# amp_schematic1.net
KiCad netlist of a schematic drawn in EAGLE
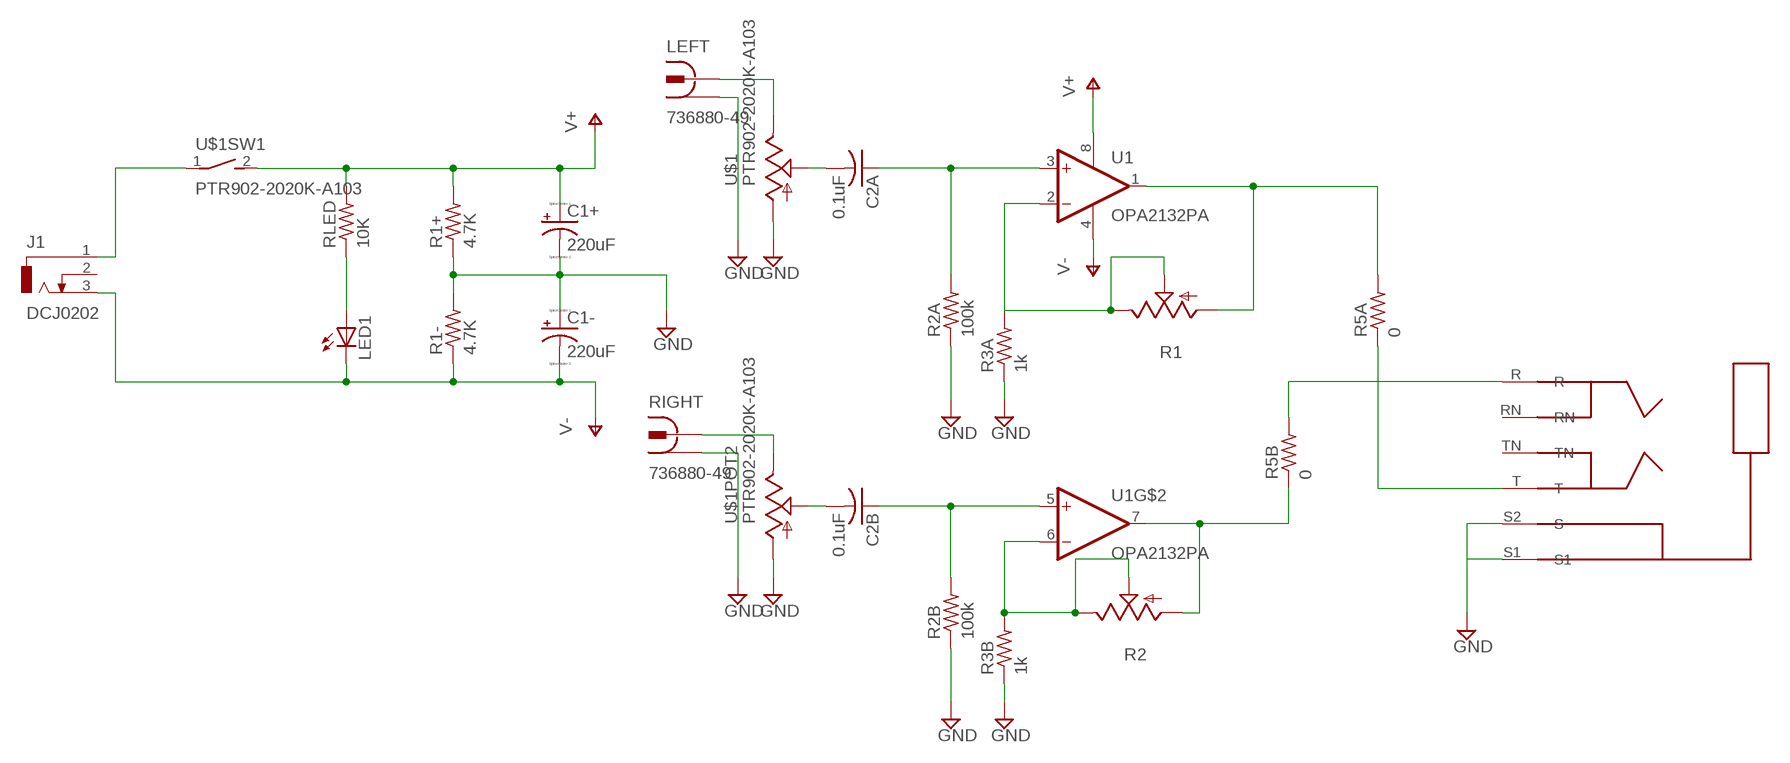
[diagram p0: schematic, sheet 1]

(export (version "E")
  (design (tool "Eeschema 10.0.6"))
  (components
    (comp (ref "C1+")
      (value "220uF")
      (footprint "eagle-import:E3,5-8")
      (libsource (lib "eagle-import") (part "CPOL-USE3.5-8"))
    )
    (comp (ref "C1-")
      (value "220uF")
      (footprint "eagle-import:E3,5-8")
      (libsource (lib "eagle-import") (part "CPOL-USE3.5-8"))
    )
    (comp (ref "C2A")
      (value "0.1uF")
      (footprint "eagle-import:C050-025X075")
      (libsource (lib "eagle-import") (part "C-US050-025X075"))
    )
    (comp (ref "C2B")
      (value "0.1uF")
      (footprint "eagle-import:C050-025X075")
      (libsource (lib "eagle-import") (part "C-US050-025X075"))
    )
    (comp (ref "J1")
      (value "DCJ0202")
      (footprint "eagle-import:DCJ0202")
      (libsource (lib "eagle-import") (part "DCJ0202"))
    )
    (comp (ref "LED1")
      (value "LED5MM")
      (footprint "eagle-import:LED5MM")
      (libsource (lib "eagle-import") (part "LED5MM"))
    )
    (comp (ref "LEFT")
      (value "736880-49")
      (footprint "eagle-import:736880-49")
      (libsource (lib "eagle-import") (part "736880-49"))
    )
    (comp (ref "R1")
      (value "TRIM_US-B25U")
      (footprint "eagle-import:B25U")
      (libsource (lib "eagle-import") (part "TRIM_US-B25U"))
    )
    (comp (ref "R1+")
      (value "4.7K")
      (footprint "eagle-import:0204V")
      (libsource (lib "eagle-import") (part "R-US_0204/2V"))
    )
    (comp (ref "R1-")
      (value "4.7K")
      (footprint "eagle-import:0204V")
      (libsource (lib "eagle-import") (part "R-US_0204/2V"))
    )
    (comp (ref "R2")
      (value "TRIM_US-B25U")
      (footprint "eagle-import:B25U")
      (libsource (lib "eagle-import") (part "TRIM_US-B25U"))
    )
    (comp (ref "R2A")
      (value "100k")
      (footprint "eagle-import:0204V")
      (libsource (lib "eagle-import") (part "R-US_0204/2V"))
    )
    (comp (ref "R2B")
      (value "100k")
      (footprint "eagle-import:0204V")
      (libsource (lib "eagle-import") (part "R-US_0204/2V"))
    )
    (comp (ref "R3A")
      (value "1k")
      (footprint "eagle-import:0204V")
      (libsource (lib "eagle-import") (part "R-US_0204/2V"))
    )
    (comp (ref "R3B")
      (value "1k")
      (footprint "eagle-import:0204V")
      (libsource (lib "eagle-import") (part "R-US_0204/2V"))
    )
    (comp (ref "R5A")
      (value "0")
      (footprint "eagle-import:0204V")
      (libsource (lib "eagle-import") (part "R-US_0204/2V"))
    )
    (comp (ref "R5B")
      (value "0")
      (footprint "eagle-import:0204V")
      (libsource (lib "eagle-import") (part "R-US_0204/2V"))
    )
    (comp (ref "RIGHT")
      (value "736880-49")
      (footprint "eagle-import:736880-49")
      (libsource (lib "eagle-import") (part "736880-49"))
    )
    (comp (ref "RLED")
      (value "10K")
      (footprint "eagle-import:0204V")
      (libsource (lib "eagle-import") (part "R-US_0204/2V"))
    )
    (comp (ref "U$1")
      (value "PTR902-2020K-A103")
      (footprint "eagle-import:PTR902")
      (libsource (lib "eagle-import") (part "PTR902-2020K-A103"))
    )
    (comp (ref "U$2")
      (value "STEROJACK")
      (footprint "eagle-import:STEREOJACK")
      (libsource (lib "eagle-import") (part "STEROJACK"))
    )
    (comp (ref "U1")
      (value "OPA2132PA")
      (footprint "eagle-import:DIP254P762X508-8")
      (fields (field (name "DIGI-KEY_PART_NUMBER") "OPA2132PA-ND") (field (name "MF") "Texas Instruments"))
      (libsource (lib "eagle-import") (part "OPA2132PA"))
    )
  )
  (nets
    (net (code "1") (name "GND") (class "Default")
      (node (ref "C1+") (pin "-") (pinfunction "-_-") (pintype "passive"))
      (node (ref "C1-") (pin "+") (pinfunction "+_+") (pintype "passive"))
      (node (ref "LEFT") (pin "1") (pinfunction "1_1") (pintype "passive"))
      (node (ref "LEFT") (pin "1@1") (pinfunction "1_1@1") (pintype "passive"))
      (node (ref "LEFT") (pin "1@2") (pinfunction "1_1@2") (pintype "passive"))
      (node (ref "R1+") (pin "1") (pinfunction "1_1") (pintype "passive"))
      (node (ref "R1-") (pin "2") (pinfunction "2_2") (pintype "passive"))
      (node (ref "R2A") (pin "1") (pinfunction "1_1") (pintype "passive"))
      (node (ref "R2B") (pin "1") (pinfunction "1_1") (pintype "passive"))
      (node (ref "R3A") (pin "1") (pinfunction "1_1") (pintype "passive"))
      (node (ref "R3B") (pin "1") (pinfunction "1_1") (pintype "passive"))
      (node (ref "RIGHT") (pin "1") (pinfunction "1_1") (pintype "passive"))
      (node (ref "RIGHT") (pin "1@1") (pinfunction "1_1@1") (pintype "passive"))
      (node (ref "RIGHT") (pin "1@2") (pinfunction "1_1@2") (pintype "passive"))
      (node (ref "U$1") (pin "1A") (pinfunction "A_1A") (pintype "passive"))
      (node (ref "U$1") (pin "1B") (pinfunction "A_1B") (pintype "passive"))
      (node (ref "U$2") (pin "S1") (pinfunction "S1_S1") (pintype "bidirectional"))
      (node (ref "U$2") (pin "S2") (pinfunction "S_S2") (pintype "bidirectional"))
    )
    (net (code "2") (name "Net-(LED1-PadA)") (class "Default")
      (node (ref "LED1") (pin "A") (pinfunction "A_A") (pintype "passive"))
      (node (ref "RLED") (pin "1") (pinfunction "1_1") (pintype "passive"))
    )
    (net (code "3") (name "Net-(R5A-Pad1)") (class "Default")
      (node (ref "R5A") (pin "1") (pinfunction "1_1") (pintype "passive"))
      (node (ref "U$2") (pin "T") (pinfunction "T_T") (pintype "bidirectional"))
    )
    (net (code "4") (name "Net-(R5B-Pad2)") (class "Default")
      (node (ref "R5B") (pin "2") (pinfunction "2_2") (pintype "passive"))
      (node (ref "U$2") (pin "R") (pinfunction "R_R") (pintype "bidirectional"))
    )
    (net (code "5") (name "Net-(U$1A-E)") (class "Default")
      (node (ref "LEFT") (pin "2") (pinfunction "2_2") (pintype "passive"))
      (node (ref "U$1") (pin "3A") (pinfunction "E_3A") (pintype "passive"))
    )
    (net (code "6") (name "Net-(U$1A-S)") (class "Default")
      (node (ref "C2A") (pin "2") (pinfunction "2_2") (pintype "passive"))
      (node (ref "U$1") (pin "2A") (pinfunction "S_2A") (pintype "passive"))
    )
    (net (code "7") (name "Net-(U$1B-E)") (class "Default")
      (node (ref "RIGHT") (pin "2") (pinfunction "2_2") (pintype "passive"))
      (node (ref "U$1") (pin "3B") (pinfunction "E_3B") (pintype "passive"))
    )
    (net (code "8") (name "Net-(U$1B-S)") (class "Default")
      (node (ref "C2B") (pin "2") (pinfunction "2_2") (pintype "passive"))
      (node (ref "U$1") (pin "2B") (pinfunction "S_2B") (pintype "passive"))
    )
    (net (code "9") (name "Net-(U$1C-P)") (class "Default")
      (node (ref "J1") (pin "1") (pinfunction "1_1") (pintype "passive"))
      (node (ref "U$1") (pin "1") (pinfunction "P_1") (pintype "passive"))
    )
    (net (code "10") (name "Net-(U1A-+INA)") (class "Default")
      (node (ref "C2A") (pin "1") (pinfunction "1_1") (pintype "passive"))
      (node (ref "R2A") (pin "2") (pinfunction "2_2") (pintype "passive"))
      (node (ref "U1") (pin "3") (pinfunction "+INA_3") (pintype "input"))
    )
    (net (code "11") (name "Net-(U1A--INA)") (class "Default")
      (node (ref "R1") (pin "E") (pinfunction "E_E") (pintype "passive"))
      (node (ref "R1") (pin "S") (pinfunction "S_S") (pintype "passive"))
      (node (ref "R3A") (pin "2") (pinfunction "2_2") (pintype "passive"))
      (node (ref "U1") (pin "2") (pinfunction "-INA_2") (pintype "input"))
    )
    (net (code "12") (name "Net-(U1A-OUTA)") (class "Default")
      (node (ref "R1") (pin "A") (pinfunction "A_A") (pintype "passive"))
      (node (ref "R5A") (pin "2") (pinfunction "2_2") (pintype "passive"))
      (node (ref "U1") (pin "1") (pinfunction "OUTA_1") (pintype "output"))
    )
    (net (code "13") (name "Net-(U1B-+INB)") (class "Default")
      (node (ref "C2B") (pin "1") (pinfunction "1_1") (pintype "passive"))
      (node (ref "R2B") (pin "2") (pinfunction "2_2") (pintype "passive"))
      (node (ref "U1") (pin "5") (pinfunction "+INB_5") (pintype "input"))
    )
    (net (code "14") (name "Net-(U1B--INB)") (class "Default")
      (node (ref "R2") (pin "E") (pinfunction "E_E") (pintype "passive"))
      (node (ref "R2") (pin "S") (pinfunction "S_S") (pintype "passive"))
      (node (ref "R3B") (pin "2") (pinfunction "2_2") (pintype "passive"))
      (node (ref "U1") (pin "6") (pinfunction "-INB_6") (pintype "input"))
    )
    (net (code "15") (name "Net-(U1B-OUTB)") (class "Default")
      (node (ref "R2") (pin "A") (pinfunction "A_A") (pintype "passive"))
      (node (ref "R5B") (pin "1") (pinfunction "1_1") (pintype "passive"))
      (node (ref "U1") (pin "7") (pinfunction "OUTB_7") (pintype "output"))
    )
    (net (code "16") (name "V+") (class "Default")
      (node (ref "C1+") (pin "+") (pinfunction "+_+") (pintype "passive"))
      (node (ref "R1+") (pin "2") (pinfunction "2_2") (pintype "passive"))
      (node (ref "RLED") (pin "2") (pinfunction "2_2") (pintype "passive"))
      (node (ref "U$1") (pin "2") (pinfunction "S_2") (pintype "passive"))
      (node (ref "U1") (pin "8") (pinfunction "V+_8") (pintype "power_in"))
    )
    (net (code "17") (name "V-") (class "Default")
      (node (ref "C1-") (pin "-") (pinfunction "-_-") (pintype "passive"))
      (node (ref "J1") (pin "3") (pinfunction "3_3") (pintype "passive"))
      (node (ref "LED1") (pin "K") (pinfunction "C_K") (pintype "passive"))
      (node (ref "R1-") (pin "1") (pinfunction "1_1") (pintype "passive"))
      (node (ref "U1") (pin "4") (pinfunction "V-_4") (pintype "power_in"))
    )
    (net (code "18") (name "unconnected-(J1-Pad2)") (class "Default")
      (node (ref "J1") (pin "2") (pinfunction "2_2") (pintype "passive"))
    )
    (net (code "19") (name "unconnected-(U$2-PadRN)") (class "Default")
      (node (ref "U$2") (pin "RN") (pinfunction "RN_RN") (pintype "bidirectional"))
    )
    (net (code "20") (name "unconnected-(U$2-PadTN)") (class "Default")
      (node (ref "U$2") (pin "TN") (pinfunction "TN_TN") (pintype "bidirectional"))
    )
  )
)
